# fmc.net
KiCad netlist of a schematic drawn in EAGLE
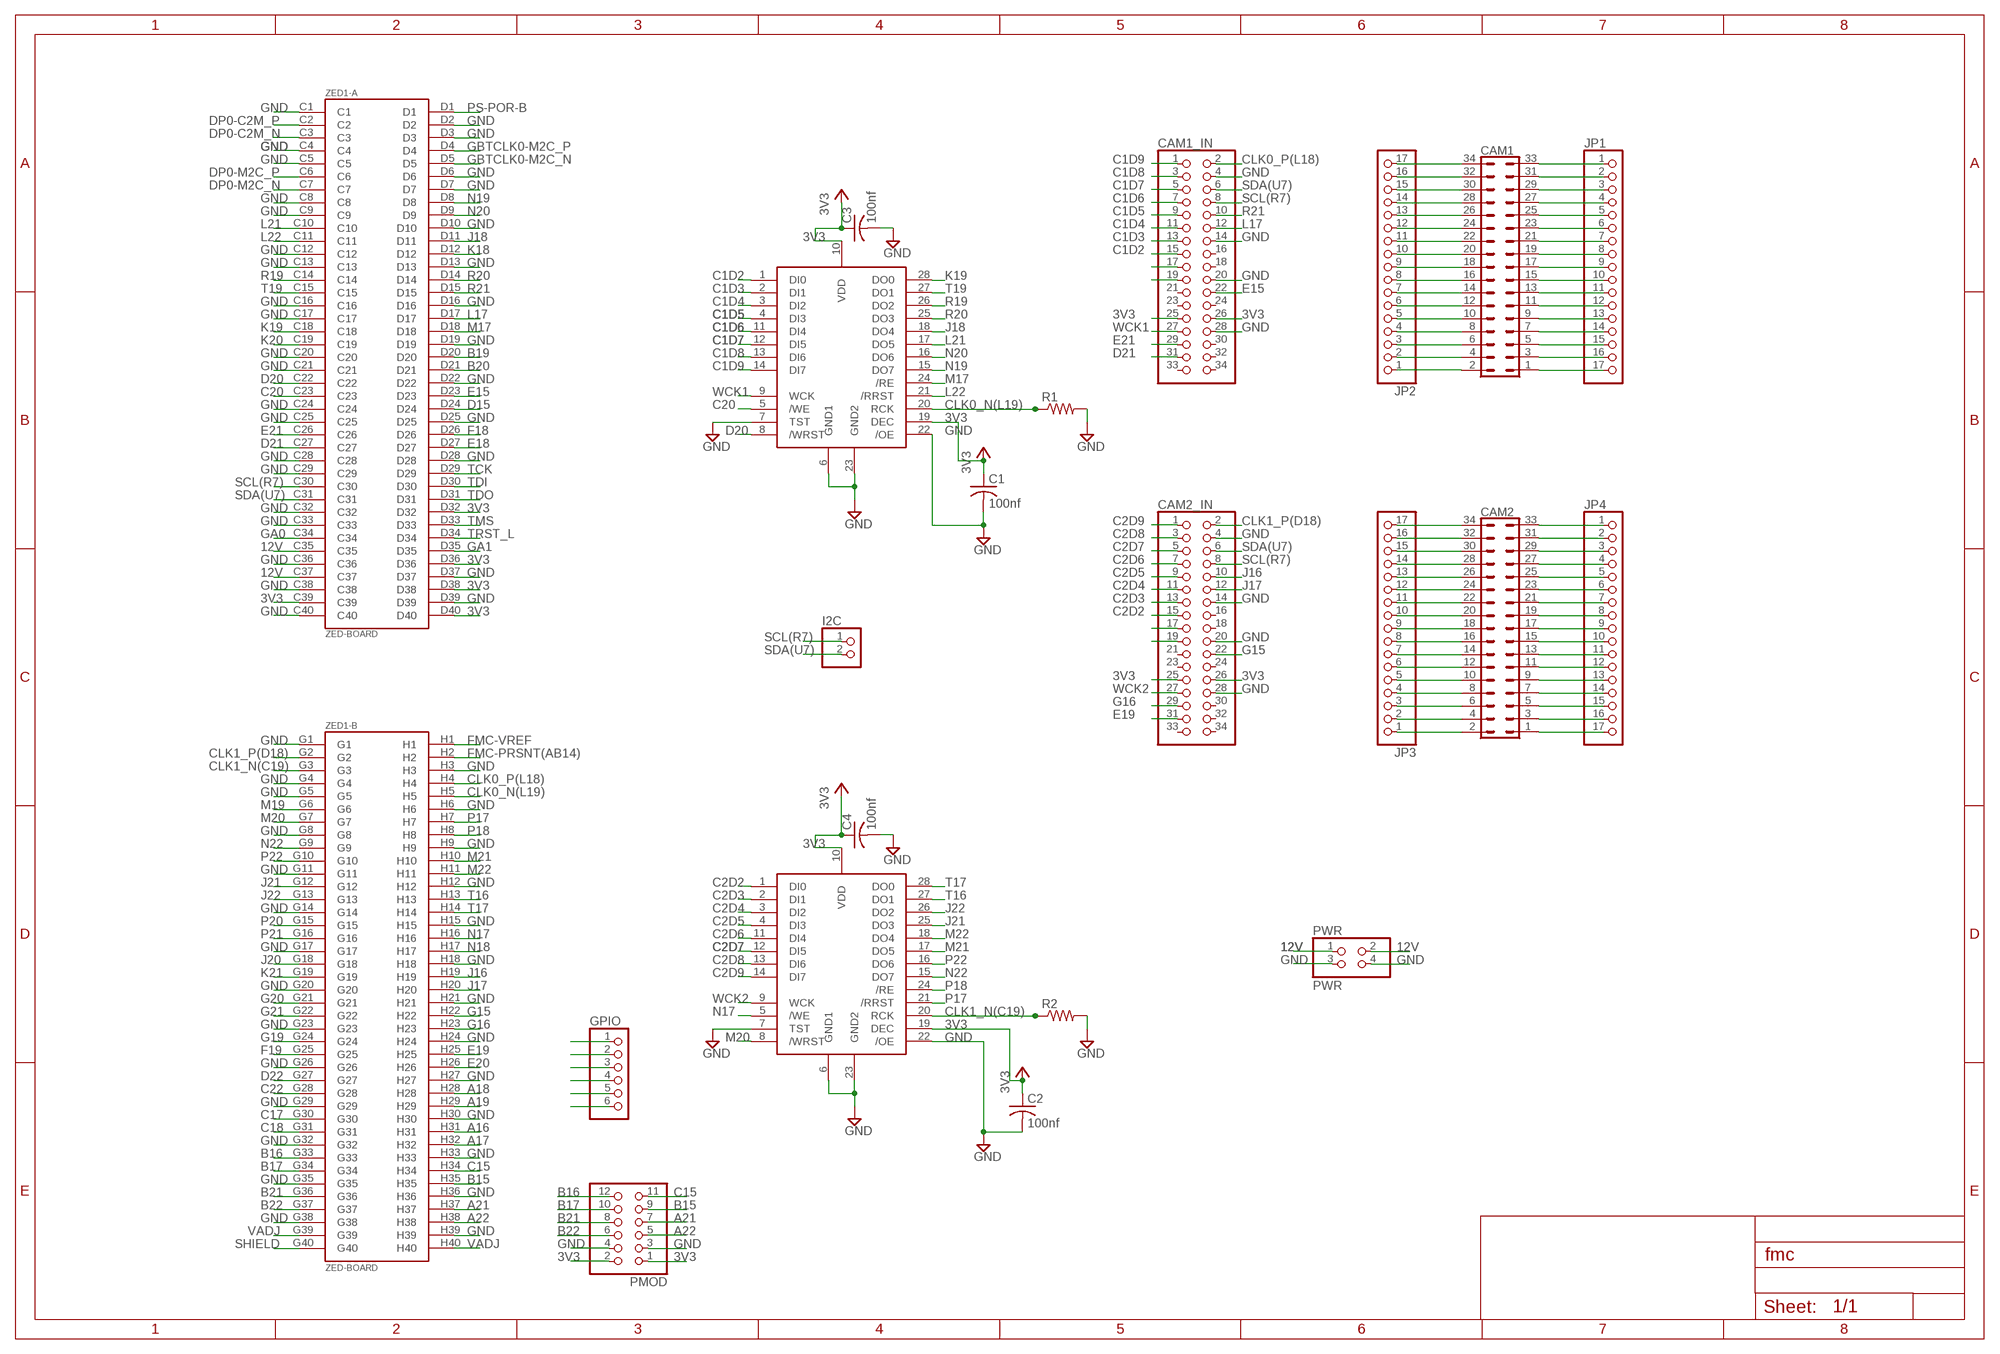
[diagram p0: schematic, sheet 1]

(export (version "E")
  (design (tool "Eeschema 10.0.6"))
  (components
    (comp (ref "AL422B_2")
      (value "CAM2_FIFO")
      (footprint "eagle-import:SOP28")
      (libsource (lib "eagle-import") (part "AL422B"))
    )
    (comp (ref "ALA22B_1")
      (value "CAM1_FIFO")
      (footprint "eagle-import:SOP28")
      (libsource (lib "eagle-import") (part "AL422B"))
    )
    (comp (ref "C1")
      (value "100nf")
      (footprint "eagle-import:C025-024X044")
      (libsource (lib "eagle-import") (part "C-US025-024X044"))
    )
    (comp (ref "C2")
      (value "100nf")
      (footprint "eagle-import:C025-024X044")
      (libsource (lib "eagle-import") (part "C-US025-024X044"))
    )
    (comp (ref "C3")
      (value "100nf")
      (footprint "eagle-import:C025-024X044")
      (libsource (lib "eagle-import") (part "C-US025-024X044"))
    )
    (comp (ref "C4")
      (value "100nf")
      (footprint "eagle-import:C025-024X044")
      (libsource (lib "eagle-import") (part "C-US025-024X044"))
    )
    (comp (ref "CAM1")
      (value "PHB_1MM27_2X17_SNT")
      (footprint "eagle-import:PHB_1MM27_2X17_SNT")
      (libsource (lib "eagle-import") (part "PHB_1MM27_2X17_SNT"))
    )
    (comp (ref "CAM1_IN")
      (value "PINHD-2X17")
      (footprint "eagle-import:2X17")
      (libsource (lib "eagle-import") (part "PINHD-2X17"))
    )
    (comp (ref "CAM2")
      (value "PHB_1MM27_2X17_SNT")
      (footprint "eagle-import:PHB_1MM27_2X17_SNT")
      (libsource (lib "eagle-import") (part "PHB_1MM27_2X17_SNT"))
    )
    (comp (ref "CAM2_IN")
      (value "PINHD-2X17")
      (footprint "eagle-import:2X17")
      (libsource (lib "eagle-import") (part "PINHD-2X17"))
    )
    (comp (ref "GPIO")
      (value "PINHD-1X6")
      (footprint "eagle-import:1X06")
      (libsource (lib "eagle-import") (part "PINHD-1X6"))
    )
    (comp (ref "I2C")
      (value "PINHD-1X2")
      (footprint "eagle-import:1X02")
      (libsource (lib "eagle-import") (part "PINHD-1X2"))
    )
    (comp (ref "JP1")
      (value "PINHD-1X17")
      (footprint "eagle-import:1X17")
      (libsource (lib "eagle-import") (part "PINHD-1X17"))
    )
    (comp (ref "JP2")
      (value "PINHD-1X17")
      (footprint "eagle-import:1X17")
      (libsource (lib "eagle-import") (part "PINHD-1X17"))
    )
    (comp (ref "JP3")
      (value "PINHD-1X17")
      (footprint "eagle-import:1X17")
      (libsource (lib "eagle-import") (part "PINHD-1X17"))
    )
    (comp (ref "JP4")
      (value "PINHD-1X17")
      (footprint "eagle-import:1X17")
      (libsource (lib "eagle-import") (part "PINHD-1X17"))
    )
    (comp (ref "PMOD")
      (value "PINHD-2X6")
      (footprint "eagle-import:2X06")
      (libsource (lib "eagle-import") (part "PINHD-2X6"))
    )
    (comp (ref "PWR")
      (value "PWR")
      (footprint "eagle-import:2X02")
      (libsource (lib "eagle-import") (part "PINHD-2X2"))
    )
    (comp (ref "R1")
      (value "R-US_M0805")
      (footprint "eagle-import:M0805")
      (libsource (lib "eagle-import") (part "R-US_M0805"))
    )
    (comp (ref "R2")
      (value "R-US_M0805")
      (footprint "eagle-import:M0805")
      (libsource (lib "eagle-import") (part "R-US_M0805"))
    )
    (comp (ref "ZED1")
      (value "ZED-BOARD")
      (footprint "eagle-import:ASP-134604-01")
      (libsource (lib "eagle-import") (part "ZED-BOARD"))
    )
  )
  (nets
    (net (code "1") (name "/12V") (class "Default")
      (node (ref "PWR") (pin "1") (pinfunction "1_1") (pintype "passive"))
      (node (ref "PWR") (pin "2") (pinfunction "2_2") (pintype "passive"))
      (node (ref "ZED1") (pin "C35") (pinfunction "C35_C35") (pintype "bidirectional"))
      (node (ref "ZED1") (pin "C37") (pinfunction "C37_C37") (pintype "bidirectional"))
    )
    (net (code "2") (name "/A16") (class "Default")
      (node (ref "GPIO") (pin "3") (pinfunction "3_3") (pintype "passive"))
      (node (ref "ZED1") (pin "H31") (pinfunction "H31_H31") (pintype "bidirectional"))
    )
    (net (code "3") (name "/A17") (class "Default")
      (node (ref "GPIO") (pin "4") (pinfunction "4_4") (pintype "passive"))
      (node (ref "ZED1") (pin "H32") (pinfunction "H32_H32") (pintype "bidirectional"))
    )
    (net (code "4") (name "/A18") (class "Default")
      (node (ref "GPIO") (pin "1") (pinfunction "1_1") (pintype "passive"))
      (node (ref "ZED1") (pin "H28") (pinfunction "H28_H28") (pintype "bidirectional"))
    )
    (net (code "5") (name "/A19") (class "Default")
      (node (ref "GPIO") (pin "2") (pinfunction "2_2") (pintype "passive"))
      (node (ref "ZED1") (pin "H29") (pinfunction "H29_H29") (pintype "bidirectional"))
    )
    (net (code "6") (name "/A21") (class "Default")
      (node (ref "PMOD") (pin "7") (pinfunction "7_7") (pintype "passive"))
      (node (ref "ZED1") (pin "H37") (pinfunction "H37_H37") (pintype "bidirectional"))
    )
    (net (code "7") (name "/A22") (class "Default")
      (node (ref "PMOD") (pin "5") (pinfunction "5_5") (pintype "passive"))
      (node (ref "ZED1") (pin "H38") (pinfunction "H38_H38") (pintype "bidirectional"))
    )
    (net (code "8") (name "/B15") (class "Default")
      (node (ref "PMOD") (pin "9") (pinfunction "9_9") (pintype "passive"))
      (node (ref "ZED1") (pin "H35") (pinfunction "H35_H35") (pintype "bidirectional"))
    )
    (net (code "9") (name "/B16") (class "Default")
      (node (ref "PMOD") (pin "12") (pinfunction "12_12") (pintype "passive"))
      (node (ref "ZED1") (pin "G33") (pinfunction "G33_G33") (pintype "bidirectional"))
    )
    (net (code "10") (name "/B17") (class "Default")
      (node (ref "PMOD") (pin "10") (pinfunction "10_10") (pintype "passive"))
      (node (ref "ZED1") (pin "G34") (pinfunction "G34_G34") (pintype "bidirectional"))
    )
    (net (code "11") (name "/B19") (class "Default")
      (node (ref "ZED1") (pin "D20") (pinfunction "D20_D20") (pintype "bidirectional"))
    )
    (net (code "12") (name "/B20") (class "Default")
      (node (ref "ZED1") (pin "D21") (pinfunction "D21_D21") (pintype "bidirectional"))
    )
    (net (code "13") (name "/B21") (class "Default")
      (node (ref "PMOD") (pin "8") (pinfunction "8_8") (pintype "passive"))
      (node (ref "ZED1") (pin "G36") (pinfunction "G36_G36") (pintype "bidirectional"))
    )
    (net (code "14") (name "/B22") (class "Default")
      (node (ref "PMOD") (pin "6") (pinfunction "6_6") (pintype "passive"))
      (node (ref "ZED1") (pin "G37") (pinfunction "G37_G37") (pintype "bidirectional"))
    )
    (net (code "15") (name "/C1D2") (class "Default")
      (node (ref "ALA22B_1") (pin "1") (pinfunction "DI0_1") (pintype "bidirectional"))
      (node (ref "CAM1_IN") (pin "15") (pinfunction "15_15") (pintype "passive"))
    )
    (net (code "16") (name "/C1D3") (class "Default")
      (node (ref "ALA22B_1") (pin "2") (pinfunction "DI1_2") (pintype "bidirectional"))
      (node (ref "CAM1_IN") (pin "13") (pinfunction "13_13") (pintype "passive"))
    )
    (net (code "17") (name "/C1D4") (class "Default")
      (node (ref "ALA22B_1") (pin "3") (pinfunction "DI2_3") (pintype "bidirectional"))
      (node (ref "CAM1_IN") (pin "11") (pinfunction "11_11") (pintype "passive"))
    )
    (net (code "18") (name "/C1D5") (class "Default")
      (node (ref "ALA22B_1") (pin "4") (pinfunction "DI3_4") (pintype "bidirectional"))
      (node (ref "CAM1_IN") (pin "9") (pinfunction "9_9") (pintype "passive"))
    )
    (net (code "19") (name "/C1D6") (class "Default")
      (node (ref "ALA22B_1") (pin "11") (pinfunction "DI4_11") (pintype "bidirectional"))
      (node (ref "CAM1_IN") (pin "7") (pinfunction "7_7") (pintype "passive"))
    )
    (net (code "20") (name "/C1D7") (class "Default")
      (node (ref "ALA22B_1") (pin "12") (pinfunction "DI5_12") (pintype "bidirectional"))
      (node (ref "CAM1_IN") (pin "5") (pinfunction "5_5") (pintype "passive"))
    )
    (net (code "21") (name "/C1D8") (class "Default")
      (node (ref "ALA22B_1") (pin "13") (pinfunction "DI6_13") (pintype "bidirectional"))
      (node (ref "CAM1_IN") (pin "3") (pinfunction "3_3") (pintype "passive"))
    )
    (net (code "22") (name "/C1D9") (class "Default")
      (node (ref "ALA22B_1") (pin "14") (pinfunction "DI7_14") (pintype "bidirectional"))
      (node (ref "CAM1_IN") (pin "1") (pinfunction "1_1") (pintype "passive"))
    )
    (net (code "23") (name "/C2D2") (class "Default")
      (node (ref "AL422B_2") (pin "1") (pinfunction "DI0_1") (pintype "bidirectional"))
      (node (ref "CAM2_IN") (pin "15") (pinfunction "15_15") (pintype "passive"))
    )
    (net (code "24") (name "/C2D3") (class "Default")
      (node (ref "AL422B_2") (pin "2") (pinfunction "DI1_2") (pintype "bidirectional"))
      (node (ref "CAM2_IN") (pin "13") (pinfunction "13_13") (pintype "passive"))
    )
    (net (code "25") (name "/C2D4") (class "Default")
      (node (ref "AL422B_2") (pin "3") (pinfunction "DI2_3") (pintype "bidirectional"))
      (node (ref "CAM2_IN") (pin "11") (pinfunction "11_11") (pintype "passive"))
    )
    (net (code "26") (name "/C2D5") (class "Default")
      (node (ref "AL422B_2") (pin "4") (pinfunction "DI3_4") (pintype "bidirectional"))
      (node (ref "CAM2_IN") (pin "9") (pinfunction "9_9") (pintype "passive"))
    )
    (net (code "27") (name "/C2D6") (class "Default")
      (node (ref "AL422B_2") (pin "11") (pinfunction "DI4_11") (pintype "bidirectional"))
      (node (ref "CAM2_IN") (pin "7") (pinfunction "7_7") (pintype "passive"))
    )
    (net (code "28") (name "/C2D7") (class "Default")
      (node (ref "AL422B_2") (pin "12") (pinfunction "DI5_12") (pintype "bidirectional"))
      (node (ref "CAM2_IN") (pin "5") (pinfunction "5_5") (pintype "passive"))
    )
    (net (code "29") (name "/C2D8") (class "Default")
      (node (ref "AL422B_2") (pin "13") (pinfunction "DI6_13") (pintype "bidirectional"))
      (node (ref "CAM2_IN") (pin "3") (pinfunction "3_3") (pintype "passive"))
    )
    (net (code "30") (name "/C2D9") (class "Default")
      (node (ref "AL422B_2") (pin "14") (pinfunction "DI7_14") (pintype "bidirectional"))
      (node (ref "CAM2_IN") (pin "1") (pinfunction "1_1") (pintype "passive"))
    )
    (net (code "31") (name "/C15") (class "Default")
      (node (ref "PMOD") (pin "11") (pinfunction "11_11") (pintype "passive"))
      (node (ref "ZED1") (pin "H34") (pinfunction "H34_H34") (pintype "bidirectional"))
    )
    (net (code "32") (name "/C17") (class "Default")
      (node (ref "ZED1") (pin "G30") (pinfunction "G30_G30") (pintype "bidirectional"))
    )
    (net (code "33") (name "/C18") (class "Default")
      (node (ref "ZED1") (pin "G31") (pinfunction "G31_G31") (pintype "bidirectional"))
    )
    (net (code "34") (name "/C20") (class "Default")
      (node (ref "ALA22B_1") (pin "5") (pinfunction "/WE_5") (pintype "bidirectional"))
      (node (ref "ZED1") (pin "C23") (pinfunction "C23_C23") (pintype "bidirectional"))
    )
    (net (code "35") (name "/C22") (class "Default")
      (node (ref "ZED1") (pin "G28") (pinfunction "G28_G28") (pintype "bidirectional"))
    )
    (net (code "36") (name "/CLK0_N(L19)") (class "Default")
      (node (ref "ALA22B_1") (pin "20") (pinfunction "RCK_20") (pintype "bidirectional"))
      (node (ref "R1") (pin "1") (pinfunction "1_1") (pintype "passive"))
      (node (ref "ZED1") (pin "H5") (pinfunction "H5_H5") (pintype "bidirectional"))
    )
    (net (code "37") (name "/CLK0_P(L18)") (class "Default")
      (node (ref "CAM1_IN") (pin "2") (pinfunction "2_2") (pintype "passive"))
      (node (ref "ZED1") (pin "H4") (pinfunction "H4_H4") (pintype "bidirectional"))
    )
    (net (code "38") (name "/CLK1_N(C19)") (class "Default")
      (node (ref "AL422B_2") (pin "20") (pinfunction "RCK_20") (pintype "bidirectional"))
      (node (ref "R2") (pin "1") (pinfunction "1_1") (pintype "passive"))
      (node (ref "ZED1") (pin "G3") (pinfunction "G3_G3") (pintype "bidirectional"))
    )
    (net (code "39") (name "/CLK1_P(D18)") (class "Default")
      (node (ref "CAM2_IN") (pin "2") (pinfunction "2_2") (pintype "passive"))
      (node (ref "ZED1") (pin "G2") (pinfunction "G2_G2") (pintype "bidirectional"))
    )
    (net (code "40") (name "/D15") (class "Default")
      (node (ref "ZED1") (pin "D24") (pinfunction "D24_D24") (pintype "bidirectional"))
    )
    (net (code "41") (name "/D20") (class "Default")
      (node (ref "ALA22B_1") (pin "8") (pinfunction "/WRST_8") (pintype "bidirectional"))
      (node (ref "ZED1") (pin "C22") (pinfunction "C22_C22") (pintype "bidirectional"))
    )
    (net (code "42") (name "/D21") (class "Default")
      (node (ref "CAM1_IN") (pin "31") (pinfunction "31_31") (pintype "passive"))
      (node (ref "ZED1") (pin "C27") (pinfunction "C27_C27") (pintype "bidirectional"))
    )
    (net (code "43") (name "/D22") (class "Default")
      (node (ref "ZED1") (pin "G27") (pinfunction "G27_G27") (pintype "bidirectional"))
    )
    (net (code "44") (name "/DP0-C2M_N") (class "Default")
      (node (ref "ZED1") (pin "C3") (pinfunction "C3_C3") (pintype "bidirectional"))
    )
    (net (code "45") (name "/DP0-C2M_P") (class "Default")
      (node (ref "ZED1") (pin "C2") (pinfunction "C2_C2") (pintype "bidirectional"))
    )
    (net (code "46") (name "/DP0-M2C_N") (class "Default")
      (node (ref "ZED1") (pin "C7") (pinfunction "C7_C7") (pintype "bidirectional"))
    )
    (net (code "47") (name "/DP0-M2C_P") (class "Default")
      (node (ref "ZED1") (pin "C6") (pinfunction "C6_C6") (pintype "bidirectional"))
    )
    (net (code "48") (name "/E15") (class "Default")
      (node (ref "CAM1_IN") (pin "22") (pinfunction "22_22") (pintype "passive"))
      (node (ref "ZED1") (pin "D23") (pinfunction "D23_D23") (pintype "bidirectional"))
    )
    (net (code "49") (name "/E18") (class "Default")
      (node (ref "ZED1") (pin "D27") (pinfunction "D27_D27") (pintype "bidirectional"))
    )
    (net (code "50") (name "/E19") (class "Default")
      (node (ref "CAM2_IN") (pin "31") (pinfunction "31_31") (pintype "passive"))
      (node (ref "ZED1") (pin "H25") (pinfunction "H25_H25") (pintype "bidirectional"))
    )
    (net (code "51") (name "/E20") (class "Default")
      (node (ref "ZED1") (pin "H26") (pinfunction "H26_H26") (pintype "bidirectional"))
    )
    (net (code "52") (name "/E21") (class "Default")
      (node (ref "CAM1_IN") (pin "29") (pinfunction "29_29") (pintype "passive"))
      (node (ref "ZED1") (pin "C26") (pinfunction "C26_C26") (pintype "bidirectional"))
    )
    (net (code "53") (name "/F18") (class "Default")
      (node (ref "ZED1") (pin "D26") (pinfunction "D26_D26") (pintype "bidirectional"))
    )
    (net (code "54") (name "/F19") (class "Default")
      (node (ref "ZED1") (pin "G25") (pinfunction "G25_G25") (pintype "bidirectional"))
    )
    (net (code "55") (name "/FMC-PRSNT(AB14)") (class "Default")
      (node (ref "ZED1") (pin "H2") (pinfunction "H2_H2") (pintype "bidirectional"))
    )
    (net (code "56") (name "/FMC-VREF") (class "Default")
      (node (ref "ZED1") (pin "H1") (pinfunction "H1_H1") (pintype "bidirectional"))
    )
    (net (code "57") (name "/G15") (class "Default")
      (node (ref "CAM2_IN") (pin "22") (pinfunction "22_22") (pintype "passive"))
      (node (ref "ZED1") (pin "H22") (pinfunction "H22_H22") (pintype "bidirectional"))
    )
    (net (code "58") (name "/G16") (class "Default")
      (node (ref "CAM2_IN") (pin "29") (pinfunction "29_29") (pintype "passive"))
      (node (ref "ZED1") (pin "H23") (pinfunction "H23_H23") (pintype "bidirectional"))
    )
    (net (code "59") (name "/G19") (class "Default")
      (node (ref "ZED1") (pin "G24") (pinfunction "G24_G24") (pintype "bidirectional"))
    )
    (net (code "60") (name "/G20") (class "Default")
      (node (ref "ZED1") (pin "G21") (pinfunction "G21_G21") (pintype "bidirectional"))
    )
    (net (code "61") (name "/G21") (class "Default")
      (node (ref "ZED1") (pin "G22") (pinfunction "G22_G22") (pintype "bidirectional"))
    )
    (net (code "62") (name "/GA0") (class "Default")
      (node (ref "ZED1") (pin "C34") (pinfunction "C34_C34") (pintype "bidirectional"))
    )
    (net (code "63") (name "/GA1") (class "Default")
      (node (ref "ZED1") (pin "D35") (pinfunction "D35_D35") (pintype "bidirectional"))
    )
    (net (code "64") (name "/GBTCLK0-M2C_N") (class "Default")
      (node (ref "ZED1") (pin "D5") (pinfunction "D5_D5") (pintype "bidirectional"))
    )
    (net (code "65") (name "/GBTCLK0-M2C_P") (class "Default")
      (node (ref "ZED1") (pin "D4") (pinfunction "D4_D4") (pintype "bidirectional"))
    )
    (net (code "66") (name "/J16") (class "Default")
      (node (ref "CAM2_IN") (pin "10") (pinfunction "10_10") (pintype "passive"))
      (node (ref "ZED1") (pin "H19") (pinfunction "H19_H19") (pintype "bidirectional"))
    )
    (net (code "67") (name "/J17") (class "Default")
      (node (ref "CAM2_IN") (pin "12") (pinfunction "12_12") (pintype "passive"))
      (node (ref "ZED1") (pin "H20") (pinfunction "H20_H20") (pintype "bidirectional"))
    )
    (net (code "68") (name "/J18") (class "Default")
      (node (ref "ALA22B_1") (pin "18") (pinfunction "DO4_18") (pintype "bidirectional"))
      (node (ref "ZED1") (pin "D11") (pinfunction "D11_D11") (pintype "bidirectional"))
    )
    (net (code "69") (name "/J20") (class "Default")
      (node (ref "ZED1") (pin "G18") (pinfunction "G18_G18") (pintype "bidirectional"))
    )
    (net (code "70") (name "/J21") (class "Default")
      (node (ref "AL422B_2") (pin "25") (pinfunction "DO3_25") (pintype "bidirectional"))
      (node (ref "ZED1") (pin "G12") (pinfunction "G12_G12") (pintype "bidirectional"))
    )
    (net (code "71") (name "/J22") (class "Default")
      (node (ref "AL422B_2") (pin "26") (pinfunction "DO2_26") (pintype "bidirectional"))
      (node (ref "ZED1") (pin "G13") (pinfunction "G13_G13") (pintype "bidirectional"))
    )
    (net (code "72") (name "/K18") (class "Default")
      (node (ref "ZED1") (pin "D12") (pinfunction "D12_D12") (pintype "bidirectional"))
    )
    (net (code "73") (name "/K19") (class "Default")
      (node (ref "ALA22B_1") (pin "28") (pinfunction "DO0_28") (pintype "bidirectional"))
      (node (ref "ZED1") (pin "C18") (pinfunction "C18_C18") (pintype "bidirectional"))
    )
    (net (code "74") (name "/K20") (class "Default")
      (node (ref "ZED1") (pin "C19") (pinfunction "C19_C19") (pintype "bidirectional"))
    )
    (net (code "75") (name "/K21") (class "Default")
      (node (ref "ZED1") (pin "G19") (pinfunction "G19_G19") (pintype "bidirectional"))
    )
    (net (code "76") (name "/L17") (class "Default")
      (node (ref "CAM1_IN") (pin "12") (pinfunction "12_12") (pintype "passive"))
      (node (ref "ZED1") (pin "D17") (pinfunction "D17_D17") (pintype "bidirectional"))
    )
    (net (code "77") (name "/L21") (class "Default")
      (node (ref "ALA22B_1") (pin "17") (pinfunction "DO5_17") (pintype "bidirectional"))
      (node (ref "ZED1") (pin "C10") (pinfunction "C10_C10") (pintype "bidirectional"))
    )
    (net (code "78") (name "/L22") (class "Default")
      (node (ref "ALA22B_1") (pin "21") (pinfunction "/RRST_21") (pintype "bidirectional"))
      (node (ref "ZED1") (pin "C11") (pinfunction "C11_C11") (pintype "bidirectional"))
    )
    (net (code "79") (name "/M17") (class "Default")
      (node (ref "ALA22B_1") (pin "24") (pinfunction "/RE_24") (pintype "bidirectional"))
      (node (ref "ZED1") (pin "D18") (pinfunction "D18_D18") (pintype "bidirectional"))
    )
    (net (code "80") (name "/M19") (class "Default")
      (node (ref "ZED1") (pin "G6") (pinfunction "G6_G6") (pintype "bidirectional"))
    )
    (net (code "81") (name "/M20") (class "Default")
      (node (ref "AL422B_2") (pin "8") (pinfunction "/WRST_8") (pintype "bidirectional"))
      (node (ref "ZED1") (pin "G7") (pinfunction "G7_G7") (pintype "bidirectional"))
    )
    (net (code "82") (name "/M21") (class "Default")
      (node (ref "AL422B_2") (pin "17") (pinfunction "DO5_17") (pintype "bidirectional"))
      (node (ref "ZED1") (pin "H10") (pinfunction "H10_H10") (pintype "bidirectional"))
    )
    (net (code "83") (name "/M22") (class "Default")
      (node (ref "AL422B_2") (pin "18") (pinfunction "DO4_18") (pintype "bidirectional"))
      (node (ref "ZED1") (pin "H11") (pinfunction "H11_H11") (pintype "bidirectional"))
    )
    (net (code "84") (name "/N17") (class "Default")
      (node (ref "AL422B_2") (pin "5") (pinfunction "/WE_5") (pintype "bidirectional"))
      (node (ref "ZED1") (pin "H16") (pinfunction "H16_H16") (pintype "bidirectional"))
    )
    (net (code "85") (name "/N18") (class "Default")
      (node (ref "ZED1") (pin "H17") (pinfunction "H17_H17") (pintype "bidirectional"))
    )
    (net (code "86") (name "/N19") (class "Default")
      (node (ref "ALA22B_1") (pin "15") (pinfunction "DO7_15") (pintype "bidirectional"))
      (node (ref "ZED1") (pin "D8") (pinfunction "D8_D8") (pintype "bidirectional"))
    )
    (net (code "87") (name "/N20") (class "Default")
      (node (ref "ALA22B_1") (pin "16") (pinfunction "DO6_16") (pintype "bidirectional"))
      (node (ref "ZED1") (pin "D9") (pinfunction "D9_D9") (pintype "bidirectional"))
    )
    (net (code "88") (name "/N22") (class "Default")
      (node (ref "AL422B_2") (pin "15") (pinfunction "DO7_15") (pintype "bidirectional"))
      (node (ref "ZED1") (pin "G9") (pinfunction "G9_G9") (pintype "bidirectional"))
    )
    (net (code "89") (name "/P17") (class "Default")
      (node (ref "AL422B_2") (pin "21") (pinfunction "/RRST_21") (pintype "bidirectional"))
      (node (ref "ZED1") (pin "H7") (pinfunction "H7_H7") (pintype "bidirectional"))
    )
    (net (code "90") (name "/P18") (class "Default")
      (node (ref "AL422B_2") (pin "24") (pinfunction "/RE_24") (pintype "bidirectional"))
      (node (ref "ZED1") (pin "H8") (pinfunction "H8_H8") (pintype "bidirectional"))
    )
    (net (code "91") (name "/P20") (class "Default")
      (node (ref "ZED1") (pin "G15") (pinfunction "G15_G15") (pintype "bidirectional"))
    )
    (net (code "92") (name "/P21") (class "Default")
      (node (ref "ZED1") (pin "G16") (pinfunction "G16_G16") (pintype "bidirectional"))
    )
    (net (code "93") (name "/P22") (class "Default")
      (node (ref "AL422B_2") (pin "16") (pinfunction "DO6_16") (pintype "bidirectional"))
      (node (ref "ZED1") (pin "G10") (pinfunction "G10_G10") (pintype "bidirectional"))
    )
    (net (code "94") (name "/PS-POR-B") (class "Default")
      (node (ref "ZED1") (pin "D1") (pinfunction "D1_D1") (pintype "bidirectional"))
    )
    (net (code "95") (name "/R19") (class "Default")
      (node (ref "ALA22B_1") (pin "26") (pinfunction "DO2_26") (pintype "bidirectional"))
      (node (ref "ZED1") (pin "C14") (pinfunction "C14_C14") (pintype "bidirectional"))
    )
    (net (code "96") (name "/R20") (class "Default")
      (node (ref "ALA22B_1") (pin "25") (pinfunction "DO3_25") (pintype "bidirectional"))
      (node (ref "ZED1") (pin "D14") (pinfunction "D14_D14") (pintype "bidirectional"))
    )
    (net (code "97") (name "/R21") (class "Default")
      (node (ref "CAM1_IN") (pin "10") (pinfunction "10_10") (pintype "passive"))
      (node (ref "ZED1") (pin "D15") (pinfunction "D15_D15") (pintype "bidirectional"))
    )
    (net (code "98") (name "/SCL(R7)") (class "Default")
      (node (ref "CAM1_IN") (pin "8") (pinfunction "8_8") (pintype "passive"))
      (node (ref "CAM2_IN") (pin "8") (pinfunction "8_8") (pintype "passive"))
      (node (ref "I2C") (pin "1") (pinfunction "1_1") (pintype "passive"))
      (node (ref "ZED1") (pin "C30") (pinfunction "C30_C30") (pintype "bidirectional"))
    )
    (net (code "99") (name "/SDA(U7)") (class "Default")
      (node (ref "CAM1_IN") (pin "6") (pinfunction "6_6") (pintype "passive"))
      (node (ref "CAM2_IN") (pin "6") (pinfunction "6_6") (pintype "passive"))
      (node (ref "I2C") (pin "2") (pinfunction "2_2") (pintype "passive"))
      (node (ref "ZED1") (pin "C31") (pinfunction "C31_C31") (pintype "bidirectional"))
    )
    (net (code "100") (name "/SHIELD") (class "Default")
      (node (ref "ZED1") (pin "G40") (pinfunction "G40_G40") (pintype "bidirectional"))
    )
    (net (code "101") (name "/T16") (class "Default")
      (node (ref "AL422B_2") (pin "27") (pinfunction "DO1_27") (pintype "bidirectional"))
      (node (ref "ZED1") (pin "H13") (pinfunction "H13_H13") (pintype "bidirectional"))
    )
    (net (code "102") (name "/T17") (class "Default")
      (node (ref "AL422B_2") (pin "28") (pinfunction "DO0_28") (pintype "bidirectional"))
      (node (ref "ZED1") (pin "H14") (pinfunction "H14_H14") (pintype "bidirectional"))
    )
    (net (code "103") (name "/T19") (class "Default")
      (node (ref "ALA22B_1") (pin "27") (pinfunction "DO1_27") (pintype "bidirectional"))
      (node (ref "ZED1") (pin "C15") (pinfunction "C15_C15") (pintype "bidirectional"))
    )
    (net (code "104") (name "/TCK") (class "Default")
      (node (ref "ZED1") (pin "D29") (pinfunction "D29_D29") (pintype "bidirectional"))
    )
    (net (code "105") (name "/TDI") (class "Default")
      (node (ref "ZED1") (pin "D30") (pinfunction "D30_D30") (pintype "bidirectional"))
    )
    (net (code "106") (name "/TDO") (class "Default")
      (node (ref "ZED1") (pin "D31") (pinfunction "D31_D31") (pintype "bidirectional"))
    )
    (net (code "107") (name "/TMS") (class "Default")
      (node (ref "ZED1") (pin "D33") (pinfunction "D33_D33") (pintype "bidirectional"))
    )
    (net (code "108") (name "/TRST_L") (class "Default")
      (node (ref "ZED1") (pin "D34") (pinfunction "D34_D34") (pintype "bidirectional"))
    )
    (net (code "109") (name "/VADJ") (class "Default")
      (node (ref "ZED1") (pin "G39") (pinfunction "G39_G39") (pintype "bidirectional"))
      (node (ref "ZED1") (pin "H40") (pinfunction "H40_H40") (pintype "bidirectional"))
    )
    (net (code "110") (name "/WCK1") (class "Default")
      (node (ref "ALA22B_1") (pin "9") (pinfunction "WCK_9") (pintype "bidirectional"))
      (node (ref "CAM1_IN") (pin "27") (pinfunction "27_27") (pintype "passive"))
    )
    (net (code "111") (name "/WCK2") (class "Default")
      (node (ref "AL422B_2") (pin "9") (pinfunction "WCK_9") (pintype "bidirectional"))
      (node (ref "CAM2_IN") (pin "27") (pinfunction "27_27") (pintype "passive"))
    )
    (net (code "112") (name "3V3") (class "Default")
      (node (ref "AL422B_2") (pin "10") (pinfunction "VDD_10") (pintype "power_in"))
      (node (ref "AL422B_2") (pin "19") (pinfunction "DEC_19") (pintype "bidirectional"))
      (node (ref "ALA22B_1") (pin "10") (pinfunction "VDD_10") (pintype "power_in"))
      (node (ref "ALA22B_1") (pin "19") (pinfunction "DEC_19") (pintype "bidirectional"))
      (node (ref "C1") (pin "1") (pinfunction "1_1") (pintype "passive"))
      (node (ref "C2") (pin "1") (pinfunction "1_1") (pintype "passive"))
      (node (ref "C3") (pin "1") (pinfunction "1_1") (pintype "passive"))
      (node (ref "C4") (pin "1") (pinfunction "1_1") (pintype "passive"))
      (node (ref "CAM1_IN") (pin "25") (pinfunction "25_25") (pintype "passive"))
      (node (ref "CAM1_IN") (pin "26") (pinfunction "26_26") (pintype "passive"))
      (node (ref "CAM2_IN") (pin "25") (pinfunction "25_25") (pintype "passive"))
      (node (ref "CAM2_IN") (pin "26") (pinfunction "26_26") (pintype "passive"))
      (node (ref "GPIO") (pin "6") (pinfunction "6_6") (pintype "passive"))
      (node (ref "PMOD") (pin "1") (pinfunction "1_1") (pintype "passive"))
      (node (ref "PMOD") (pin "2") (pinfunction "2_2") (pintype "passive"))
      (node (ref "ZED1") (pin "C39") (pinfunction "C39_C39") (pintype "bidirectional"))
      (node (ref "ZED1") (pin "D32") (pinfunction "D32_D32") (pintype "bidirectional"))
      (node (ref "ZED1") (pin "D36") (pinfunction "D36_D36") (pintype "bidirectional"))
      (node (ref "ZED1") (pin "D38") (pinfunction "D38_D38") (pintype "bidirectional"))
      (node (ref "ZED1") (pin "D40") (pinfunction "D40_D40") (pintype "bidirectional"))
    )
    (net (code "113") (name "GND") (class "Default")
      (node (ref "AL422B_2") (pin "22") (pinfunction "/OE_22") (pintype "bidirectional"))
      (node (ref "AL422B_2") (pin "23") (pinfunction "GND2_23") (pintype "power_in"))
      (node (ref "AL422B_2") (pin "6") (pinfunction "GND1_6") (pintype "power_in"))
      (node (ref "AL422B_2") (pin "7") (pinfunction "TST_7") (pintype "bidirectional"))
      (node (ref "ALA22B_1") (pin "22") (pinfunction "/OE_22") (pintype "bidirectional"))
      (node (ref "ALA22B_1") (pin "23") (pinfunction "GND2_23") (pintype "power_in"))
      (node (ref "ALA22B_1") (pin "6") (pinfunction "GND1_6") (pintype "power_in"))
      (node (ref "ALA22B_1") (pin "7") (pinfunction "TST_7") (pintype "bidirectional"))
      (node (ref "C1") (pin "2") (pinfunction "2_2") (pintype "passive"))
      (node (ref "C2") (pin "2") (pinfunction "2_2") (pintype "passive"))
      (node (ref "C3") (pin "2") (pinfunction "2_2") (pintype "passive"))
      (node (ref "C4") (pin "2") (pinfunction "2_2") (pintype "passive"))
      (node (ref "CAM1_IN") (pin "14") (pinfunction "14_14") (pintype "passive"))
      (node (ref "CAM1_IN") (pin "20") (pinfunction "20_20") (pintype "passive"))
      (node (ref "CAM1_IN") (pin "28") (pinfunction "28_28") (pintype "passive"))
      (node (ref "CAM1_IN") (pin "4") (pinfunction "4_4") (pintype "passive"))
      (node (ref "CAM2_IN") (pin "14") (pinfunction "14_14") (pintype "passive"))
      (node (ref "CAM2_IN") (pin "20") (pinfunction "20_20") (pintype "passive"))
      (node (ref "CAM2_IN") (pin "28") (pinfunction "28_28") (pintype "passive"))
      (node (ref "CAM2_IN") (pin "4") (pinfunction "4_4") (pintype "passive"))
      (node (ref "GPIO") (pin "5") (pinfunction "5_5") (pintype "passive"))
      (node (ref "PMOD") (pin "3") (pinfunction "3_3") (pintype "passive"))
      (node (ref "PMOD") (pin "4") (pinfunction "4_4") (pintype "passive"))
      (node (ref "PWR") (pin "3") (pinfunction "3_3") (pintype "passive"))
      (node (ref "PWR") (pin "4") (pinfunction "4_4") (pintype "passive"))
      (node (ref "R1") (pin "2") (pinfunction "2_2") (pintype "passive"))
      (node (ref "R2") (pin "2") (pinfunction "2_2") (pintype "passive"))
      (node (ref "ZED1") (pin "C1") (pinfunction "C1_C1") (pintype "bidirectional"))
      (node (ref "ZED1") (pin "C12") (pinfunction "C12_C12") (pintype "bidirectional"))
      (node (ref "ZED1") (pin "C13") (pinfunction "C13_C13") (pintype "bidirectional"))
      (node (ref "ZED1") (pin "C16") (pinfunction "C16_C16") (pintype "bidirectional"))
      (node (ref "ZED1") (pin "C17") (pinfunction "C17_C17") (pintype "bidirectional"))
      (node (ref "ZED1") (pin "C20") (pinfunction "C20_C20") (pintype "bidirectional"))
      (node (ref "ZED1") (pin "C21") (pinfunction "C21_C21") (pintype "bidirectional"))
      (node (ref "ZED1") (pin "C24") (pinfunction "C24_C24") (pintype "bidirectional"))
      (node (ref "ZED1") (pin "C25") (pinfunction "C25_C25") (pintype "bidirectional"))
      (node (ref "ZED1") (pin "C28") (pinfunction "C28_C28") (pintype "bidirectional"))
      (node (ref "ZED1") (pin "C29") (pinfunction "C29_C29") (pintype "bidirectional"))
      (node (ref "ZED1") (pin "C32") (pinfunction "C32_C32") (pintype "bidirectional"))
      (node (ref "ZED1") (pin "C33") (pinfunction "C33_C33") (pintype "bidirectional"))
      (node (ref "ZED1") (pin "C36") (pinfunction "C36_C36") (pintype "bidirectional"))
      (node (ref "ZED1") (pin "C38") (pinfunction "C38_C38") (pintype "bidirectional"))
      (node (ref "ZED1") (pin "C4") (pinfunction "C4_C4") (pintype "bidirectional"))
      (node (ref "ZED1") (pin "C40") (pinfunction "C40_C40") (pintype "bidirectional"))
      (node (ref "ZED1") (pin "C5") (pinfunction "C5_C5") (pintype "bidirectional"))
      (node (ref "ZED1") (pin "C8") (pinfunction "C8_C8") (pintype "bidirectional"))
      (node (ref "ZED1") (pin "C9") (pinfunction "C9_C9") (pintype "bidirectional"))
      (node (ref "ZED1") (pin "D10") (pinfunction "D10_D10") (pintype "bidirectional"))
      (node (ref "ZED1") (pin "D13") (pinfunction "D13_D13") (pintype "bidirectional"))
      (node (ref "ZED1") (pin "D16") (pinfunction "D16_D16") (pintype "bidirectional"))
      (node (ref "ZED1") (pin "D19") (pinfunction "D19_D19") (pintype "bidirectional"))
      (node (ref "ZED1") (pin "D2") (pinfunction "D2_D2") (pintype "bidirectional"))
      (node (ref "ZED1") (pin "D22") (pinfunction "D22_D22") (pintype "bidirectional"))
      (node (ref "ZED1") (pin "D25") (pinfunction "D25_D25") (pintype "bidirectional"))
      (node (ref "ZED1") (pin "D28") (pinfunction "D28_D28") (pintype "bidirectional"))
      (node (ref "ZED1") (pin "D3") (pinfunction "D3_D3") (pintype "bidirectional"))
      (node (ref "ZED1") (pin "D37") (pinfunction "D37_D37") (pintype "bidirectional"))
      (node (ref "ZED1") (pin "D39") (pinfunction "D39_D39") (pintype "bidirectional"))
      (node (ref "ZED1") (pin "D6") (pinfunction "D6_D6") (pintype "bidirectional"))
      (node (ref "ZED1") (pin "D7") (pinfunction "D7_D7") (pintype "bidirectional"))
      (node (ref "ZED1") (pin "G1") (pinfunction "G1_G1") (pintype "bidirectional"))
      (node (ref "ZED1") (pin "G11") (pinfunction "G11_G11") (pintype "bidirectional"))
      (node (ref "ZED1") (pin "G14") (pinfunction "G14_G14") (pintype "bidirectional"))
      (node (ref "ZED1") (pin "G17") (pinfunction "G17_G17") (pintype "bidirectional"))
      (node (ref "ZED1") (pin "G20") (pinfunction "G20_G20") (pintype "bidirectional"))
      (node (ref "ZED1") (pin "G23") (pinfunction "G23_G23") (pintype "bidirectional"))
      (node (ref "ZED1") (pin "G26") (pinfunction "G26_G26") (pintype "bidirectional"))
      (node (ref "ZED1") (pin "G29") (pinfunction "G29_G29") (pintype "bidirectional"))
      (node (ref "ZED1") (pin "G32") (pinfunction "G32_G32") (pintype "bidirectional"))
      (node (ref "ZED1") (pin "G35") (pinfunction "G35_G35") (pintype "bidirectional"))
      (node (ref "ZED1") (pin "G38") (pinfunction "G38_G38") (pintype "bidirectional"))
      (node (ref "ZED1") (pin "G4") (pinfunction "G4_G4") (pintype "bidirectional"))
      (node (ref "ZED1") (pin "G5") (pinfunction "G5_G5") (pintype "bidirectional"))
      (node (ref "ZED1") (pin "G8") (pinfunction "G8_G8") (pintype "bidirectional"))
      (node (ref "ZED1") (pin "H12") (pinfunction "H12_H12") (pintype "bidirectional"))
      (node (ref "ZED1") (pin "H15") (pinfunction "H15_H15") (pintype "bidirectional"))
      (node (ref "ZED1") (pin "H18") (pinfunction "H18_H18") (pintype "bidirectional"))
      (node (ref "ZED1") (pin "H21") (pinfunction "H21_H21") (pintype "bidirectional"))
      (node (ref "ZED1") (pin "H24") (pinfunction "H24_H24") (pintype "bidirectional"))
      (node (ref "ZED1") (pin "H27") (pinfunction "H27_H27") (pintype "bidirectional"))
      (node (ref "ZED1") (pin "H3") (pinfunction "H3_H3") (pintype "bidirectional"))
      (node (ref "ZED1") (pin "H30") (pinfunction "H30_H30") (pintype "bidirectional"))
      (node (ref "ZED1") (pin "H33") (pinfunction "H33_H33") (pintype "bidirectional"))
      (node (ref "ZED1") (pin "H36") (pinfunction "H36_H36") (pintype "bidirectional"))
      (node (ref "ZED1") (pin "H39") (pinfunction "H39_H39") (pintype "bidirectional"))
      (node (ref "ZED1") (pin "H6") (pinfunction "H6_H6") (pintype "bidirectional"))
      (node (ref "ZED1") (pin "H9") (pinfunction "H9_H9") (pintype "bidirectional"))
    )
    (net (code "114") (name "Net-(CAM1-Pad1)") (class "Default")
      (node (ref "CAM1") (pin "1") (pinfunction "1_1") (pintype "passive"))
      (node (ref "JP1") (pin "17") (pinfunction "17_17") (pintype "passive"))
    )
    (net (code "115") (name "Net-(CAM1-Pad2)") (class "Default")
      (node (ref "CAM1") (pin "2") (pinfunction "2_2") (pintype "passive"))
      (node (ref "JP2") (pin "1") (pinfunction "1_1") (pintype "passive"))
    )
    (net (code "116") (name "Net-(CAM1-Pad3)") (class "Default")
      (node (ref "CAM1") (pin "3") (pinfunction "3_3") (pintype "passive"))
      (node (ref "JP1") (pin "16") (pinfunction "16_16") (pintype "passive"))
    )
    (net (code "117") (name "Net-(CAM1-Pad4)") (class "Default")
      (node (ref "CAM1") (pin "4") (pinfunction "4_4") (pintype "passive"))
      (node (ref "JP2") (pin "2") (pinfunction "2_2") (pintype "passive"))
    )
    (net (code "118") (name "Net-(CAM1-Pad5)") (class "Default")
      (node (ref "CAM1") (pin "5") (pinfunction "5_5") (pintype "passive"))
      (node (ref "JP1") (pin "15") (pinfunction "15_15") (pintype "passive"))
    )
    (net (code "119") (name "Net-(CAM1-Pad6)") (class "Default")
      (node (ref "CAM1") (pin "6") (pinfunction "6_6") (pintype "passive"))
      (node (ref "JP2") (pin "3") (pinfunction "3_3") (pintype "passive"))
    )
    (net (code "120") (name "Net-(CAM1-Pad7)") (class "Default")
      (node (ref "CAM1") (pin "7") (pinfunction "7_7") (pintype "passive"))
      (node (ref "JP1") (pin "14") (pinfunction "14_14") (pintype "passive"))
    )
    (net (code "121") (name "Net-(CAM1-Pad8)") (class "Default")
      (node (ref "CAM1") (pin "8") (pinfunction "8_8") (pintype "passive"))
      (node (ref "JP2") (pin "4") (pinfunction "4_4") (pintype "passive"))
    )
    (net (code "122") (name "Net-(CAM1-Pad9)") (class "Default")
      (node (ref "CAM1") (pin "9") (pinfunction "9_9") (pintype "passive"))
      (node (ref "JP1") (pin "13") (pinfunction "13_13") (pintype "passive"))
    )
    (net (code "123") (name "Net-(CAM1-Pad10)") (class "Default")
      (node (ref "CAM1") (pin "10") (pinfunction "10_10") (pintype "passive"))
      (node (ref "JP2") (pin "5") (pinfunction "5_5") (pintype "passive"))
    )
    (net (code "124") (name "Net-(CAM1-Pad11)") (class "Default")
      (node (ref "CAM1") (pin "11") (pinfunction "11_11") (pintype "passive"))
      (node (ref "JP1") (pin "12") (pinfunction "12_12") (pintype "passive"))
    )
    (net (code "125") (name "Net-(CAM1-Pad12)") (class "Default")
      (node (ref "CAM1") (pin "12") (pinfunction "12_12") (pintype "passive"))
      (node (ref "JP2") (pin "6") (pinfunction "6_6") (pintype "passive"))
    )
    (net (code "126") (name "Net-(CAM1-Pad13)") (class "Default")
      (node (ref "CAM1") (pin "13") (pinfunction "13_13") (pintype "passive"))
      (node (ref "JP1") (pin "11") (pinfunction "11_11") (pintype "passive"))
    )
    (net (code "127") (name "Net-(CAM1-Pad14)") (class "Default")
      (node (ref "CAM1") (pin "14") (pinfunction "14_14") (pintype "passive"))
      (node (ref "JP2") (pin "7") (pinfunction "7_7") (pintype "passive"))
    )
    (net (code "128") (name "Net-(CAM1-Pad15)") (class "Default")
      (node (ref "CAM1") (pin "15") (pinfunction "15_15") (pintype "passive"))
      (node (ref "JP1") (pin "10") (pinfunction "10_10") (pintype "passive"))
    )
    (net (code "129") (name "Net-(CAM1-Pad16)") (class "Default")
      (node (ref "CAM1") (pin "16") (pinfunction "16_16") (pintype "passive"))
      (node (ref "JP2") (pin "8") (pinfunction "8_8") (pintype "passive"))
    )
    (net (code "130") (name "Net-(CAM1-Pad17)") (class "Default")
      (node (ref "CAM1") (pin "17") (pinfunction "17_17") (pintype "passive"))
      (node (ref "JP1") (pin "9") (pinfunction "9_9") (pintype "passive"))
    )
    (net (code "131") (name "Net-(CAM1-Pad18)") (class "Default")
      (node (ref "CAM1") (pin "18") (pinfunction "18_18") (pintype "passive"))
      (node (ref "JP2") (pin "9") (pinfunction "9_9") (pintype "passive"))
    )
    (net (code "132") (name "Net-(CAM1-Pad19)") (class "Default")
      (node (ref "CAM1") (pin "19") (pinfunction "19_19") (pintype "passive"))
      (node (ref "JP1") (pin "8") (pinfunction "8_8") (pintype "passive"))
    )
    (net (code "133") (name "Net-(CAM1-Pad20)") (class "Default")
      (node (ref "CAM1") (pin "20") (pinfunction "20_20") (pintype "passive"))
      (node (ref "JP2") (pin "10") (pinfunction "10_10") (pintype "passive"))
    )
    (net (code "134") (name "Net-(CAM1-Pad21)") (class "Default")
      (node (ref "CAM1") (pin "21") (pinfunction "21_21") (pintype "passive"))
      (node (ref "JP1") (pin "7") (pinfunction "7_7") (pintype "passive"))
    )
    (net (code "135") (name "Net-(CAM1-Pad22)") (class "Default")
      (node (ref "CAM1") (pin "22") (pinfunction "22_22") (pintype "passive"))
      (node (ref "JP2") (pin "11") (pinfunction "11_11") (pintype "passive"))
    )
    (net (code "136") (name "Net-(CAM1-Pad23)") (class "Default")
      (node (ref "CAM1") (pin "23") (pinfunction "23_23") (pintype "passive"))
      (node (ref "JP1") (pin "6") (pinfunction "6_6") (pintype "passive"))
    )
    (net (code "137") (name "Net-(CAM1-Pad24)") (class "Default")
      (node (ref "CAM1") (pin "24") (pinfunction "24_24") (pintype "passive"))
      (node (ref "JP2") (pin "12") (pinfunction "12_12") (pintype "passive"))
    )
    (net (code "138") (name "Net-(CAM1-Pad25)") (class "Default")
      (node (ref "CAM1") (pin "25") (pinfunction "25_25") (pintype "passive"))
      (node (ref "JP1") (pin "5") (pinfunction "5_5") (pintype "passive"))
    )
    (net (code "139") (name "Net-(CAM1-Pad26)") (class "Default")
      (node (ref "CAM1") (pin "26") (pinfunction "26_26") (pintype "passive"))
      (node (ref "JP2") (pin "13") (pinfunction "13_13") (pintype "passive"))
    )
    (net (code "140") (name "Net-(CAM1-Pad27)") (class "Default")
      (node (ref "CAM1") (pin "27") (pinfunction "27_27") (pintype "passive"))
      (node (ref "JP1") (pin "4") (pinfunction "4_4") (pintype "passive"))
    )
    (net (code "141") (name "Net-(CAM1-Pad28)") (class "Default")
      (node (ref "CAM1") (pin "28") (pinfunction "28_28") (pintype "passive"))
      (node (ref "JP2") (pin "14") (pinfunction "14_14") (pintype "passive"))
    )
    (net (code "142") (name "Net-(CAM1-Pad29)") (class "Default")
      (node (ref "CAM1") (pin "29") (pinfunction "29_29") (pintype "passive"))
      (node (ref "JP1") (pin "3") (pinfunction "3_3") (pintype "passive"))
    )
    (net (code "143") (name "Net-(CAM1-Pad30)") (class "Default")
      (node (ref "CAM1") (pin "30") (pinfunction "30_30") (pintype "passive"))
      (node (ref "JP2") (pin "15") (pinfunction "15_15") (pintype "passive"))
    )
    (net (code "144") (name "Net-(CAM1-Pad31)") (class "Default")
      (node (ref "CAM1") (pin "31") (pinfunction "31_31") (pintype "passive"))
      (node (ref "JP1") (pin "2") (pinfunction "2_2") (pintype "passive"))
    )
    (net (code "145") (name "Net-(CAM1-Pad32)") (class "Default")
      (node (ref "CAM1") (pin "32") (pinfunction "32_32") (pintype "passive"))
      (node (ref "JP2") (pin "16") (pinfunction "16_16") (pintype "passive"))
    )
    (net (code "146") (name "Net-(CAM1-Pad33)") (class "Default")
      (node (ref "CAM1") (pin "33") (pinfunction "33_33") (pintype "passive"))
      (node (ref "JP1") (pin "1") (pinfunction "1_1") (pintype "passive"))
    )
    (net (code "147") (name "Net-(CAM1-Pad34)") (class "Default")
      (node (ref "CAM1") (pin "34") (pinfunction "34_34") (pintype "passive"))
      (node (ref "JP2") (pin "17") (pinfunction "17_17") (pintype "passive"))
    )
    (net (code "148") (name "Net-(CAM2-Pad1)") (class "Default")
      (node (ref "CAM2") (pin "1") (pinfunction "1_1") (pintype "passive"))
      (node (ref "JP4") (pin "17") (pinfunction "17_17") (pintype "passive"))
    )
    (net (code "149") (name "Net-(CAM2-Pad2)") (class "Default")
      (node (ref "CAM2") (pin "2") (pinfunction "2_2") (pintype "passive"))
      (node (ref "JP3") (pin "1") (pinfunction "1_1") (pintype "passive"))
    )
    (net (code "150") (name "Net-(CAM2-Pad3)") (class "Default")
      (node (ref "CAM2") (pin "3") (pinfunction "3_3") (pintype "passive"))
      (node (ref "JP4") (pin "16") (pinfunction "16_16") (pintype "passive"))
    )
    (net (code "151") (name "Net-(CAM2-Pad4)") (class "Default")
      (node (ref "CAM2") (pin "4") (pinfunction "4_4") (pintype "passive"))
      (node (ref "JP3") (pin "2") (pinfunction "2_2") (pintype "passive"))
    )
    (net (code "152") (name "Net-(CAM2-Pad5)") (class "Default")
      (node (ref "CAM2") (pin "5") (pinfunction "5_5") (pintype "passive"))
      (node (ref "JP4") (pin "15") (pinfunction "15_15") (pintype "passive"))
    )
    (net (code "153") (name "Net-(CAM2-Pad6)") (class "Default")
      (node (ref "CAM2") (pin "6") (pinfunction "6_6") (pintype "passive"))
      (node (ref "JP3") (pin "3") (pinfunction "3_3") (pintype "passive"))
    )
    (net (code "154") (name "Net-(CAM2-Pad7)") (class "Default")
      (node (ref "CAM2") (pin "7") (pinfunction "7_7") (pintype "passive"))
      (node (ref "JP4") (pin "14") (pinfunction "14_14") (pintype "passive"))
    )
    (net (code "155") (name "Net-(CAM2-Pad8)") (class "Default")
      (node (ref "CAM2") (pin "8") (pinfunction "8_8") (pintype "passive"))
      (node (ref "JP3") (pin "4") (pinfunction "4_4") (pintype "passive"))
    )
    (net (code "156") (name "Net-(CAM2-Pad9)") (class "Default")
      (node (ref "CAM2") (pin "9") (pinfunction "9_9") (pintype "passive"))
      (node (ref "JP4") (pin "13") (pinfunction "13_13") (pintype "passive"))
    )
    (net (code "157") (name "Net-(CAM2-Pad10)") (class "Default")
      (node (ref "CAM2") (pin "10") (pinfunction "10_10") (pintype "passive"))
      (node (ref "JP3") (pin "5") (pinfunction "5_5") (pintype "passive"))
    )
    (net (code "158") (name "Net-(CAM2-Pad11)") (class "Default")
      (node (ref "CAM2") (pin "11") (pinfunction "11_11") (pintype "passive"))
      (node (ref "JP4") (pin "12") (pinfunction "12_12") (pintype "passive"))
    )
    (net (code "159") (name "Net-(CAM2-Pad12)") (class "Default")
      (node (ref "CAM2") (pin "12") (pinfunction "12_12") (pintype "passive"))
      (node (ref "JP3") (pin "6") (pinfunction "6_6") (pintype "passive"))
    )
    (net (code "160") (name "Net-(CAM2-Pad13)") (class "Default")
      (node (ref "CAM2") (pin "13") (pinfunction "13_13") (pintype "passive"))
      (node (ref "JP4") (pin "11") (pinfunction "11_11") (pintype "passive"))
    )
    (net (code "161") (name "Net-(CAM2-Pad14)") (class "Default")
      (node (ref "CAM2") (pin "14") (pinfunction "14_14") (pintype "passive"))
      (node (ref "JP3") (pin "7") (pinfunction "7_7") (pintype "passive"))
    )
    (net (code "162") (name "Net-(CAM2-Pad15)") (class "Default")
      (node (ref "CAM2") (pin "15") (pinfunction "15_15") (pintype "passive"))
      (node (ref "JP4") (pin "10") (pinfunction "10_10") (pintype "passive"))
    )
    (net (code "163") (name "Net-(CAM2-Pad16)") (class "Default")
      (node (ref "CAM2") (pin "16") (pinfunction "16_16") (pintype "passive"))
      (node (ref "JP3") (pin "8") (pinfunction "8_8") (pintype "passive"))
    )
    (net (code "164") (name "Net-(CAM2-Pad17)") (class "Default")
      (node (ref "CAM2") (pin "17") (pinfunction "17_17") (pintype "passive"))
      (node (ref "JP4") (pin "9") (pinfunction "9_9") (pintype "passive"))
    )
    (net (code "165") (name "Net-(CAM2-Pad18)") (class "Default")
      (node (ref "CAM2") (pin "18") (pinfunction "18_18") (pintype "passive"))
      (node (ref "JP3") (pin "9") (pinfunction "9_9") (pintype "passive"))
    )
    (net (code "166") (name "Net-(CAM2-Pad19)") (class "Default")
      (node (ref "CAM2") (pin "19") (pinfunction "19_19") (pintype "passive"))
      (node (ref "JP4") (pin "8") (pinfunction "8_8") (pintype "passive"))
    )
    (net (code "167") (name "Net-(CAM2-Pad20)") (class "Default")
      (node (ref "CAM2") (pin "20") (pinfunction "20_20") (pintype "passive"))
      (node (ref "JP3") (pin "10") (pinfunction "10_10") (pintype "passive"))
    )
    (net (code "168") (name "Net-(CAM2-Pad21)") (class "Default")
      (node (ref "CAM2") (pin "21") (pinfunction "21_21") (pintype "passive"))
      (node (ref "JP4") (pin "7") (pinfunction "7_7") (pintype "passive"))
    )
    (net (code "169") (name "Net-(CAM2-Pad22)") (class "Default")
      (node (ref "CAM2") (pin "22") (pinfunction "22_22") (pintype "passive"))
      (node (ref "JP3") (pin "11") (pinfunction "11_11") (pintype "passive"))
    )
    (net (code "170") (name "Net-(CAM2-Pad23)") (class "Default")
      (node (ref "CAM2") (pin "23") (pinfunction "23_23") (pintype "passive"))
      (node (ref "JP4") (pin "6") (pinfunction "6_6") (pintype "passive"))
    )
    (net (code "171") (name "Net-(CAM2-Pad24)") (class "Default")
      (node (ref "CAM2") (pin "24") (pinfunction "24_24") (pintype "passive"))
      (node (ref "JP3") (pin "12") (pinfunction "12_12") (pintype "passive"))
    )
    (net (code "172") (name "Net-(CAM2-Pad25)") (class "Default")
      (node (ref "CAM2") (pin "25") (pinfunction "25_25") (pintype "passive"))
      (node (ref "JP4") (pin "5") (pinfunction "5_5") (pintype "passive"))
    )
    (net (code "173") (name "Net-(CAM2-Pad26)") (class "Default")
      (node (ref "CAM2") (pin "26") (pinfunction "26_26") (pintype "passive"))
      (node (ref "JP3") (pin "13") (pinfunction "13_13") (pintype "passive"))
    )
    (net (code "174") (name "Net-(CAM2-Pad27)") (class "Default")
      (node (ref "CAM2") (pin "27") (pinfunction "27_27") (pintype "passive"))
      (node (ref "JP4") (pin "4") (pinfunction "4_4") (pintype "passive"))
    )
    (net (code "175") (name "Net-(CAM2-Pad28)") (class "Default")
      (node (ref "CAM2") (pin "28") (pinfunction "28_28") (pintype "passive"))
      (node (ref "JP3") (pin "14") (pinfunction "14_14") (pintype "passive"))
    )
    (net (code "176") (name "Net-(CAM2-Pad29)") (class "Default")
      (node (ref "CAM2") (pin "29") (pinfunction "29_29") (pintype "passive"))
      (node (ref "JP4") (pin "3") (pinfunction "3_3") (pintype "passive"))
    )
    (net (code "177") (name "Net-(CAM2-Pad30)") (class "Default")
      (node (ref "CAM2") (pin "30") (pinfunction "30_30") (pintype "passive"))
      (node (ref "JP3") (pin "15") (pinfunction "15_15") (pintype "passive"))
    )
    (net (code "178") (name "Net-(CAM2-Pad31)") (class "Default")
      (node (ref "CAM2") (pin "31") (pinfunction "31_31") (pintype "passive"))
      (node (ref "JP4") (pin "2") (pinfunction "2_2") (pintype "passive"))
    )
    (net (code "179") (name "Net-(CAM2-Pad32)") (class "Default")
      (node (ref "CAM2") (pin "32") (pinfunction "32_32") (pintype "passive"))
      (node (ref "JP3") (pin "16") (pinfunction "16_16") (pintype "passive"))
    )
    (net (code "180") (name "Net-(CAM2-Pad33)") (class "Default")
      (node (ref "CAM2") (pin "33") (pinfunction "33_33") (pintype "passive"))
      (node (ref "JP4") (pin "1") (pinfunction "1_1") (pintype "passive"))
    )
    (net (code "181") (name "Net-(CAM2-Pad34)") (class "Default")
      (node (ref "CAM2") (pin "34") (pinfunction "34_34") (pintype "passive"))
      (node (ref "JP3") (pin "17") (pinfunction "17_17") (pintype "passive"))
    )
    (net (code "182") (name "unconnected-(CAM1_IN-Pad16)") (class "Default")
      (node (ref "CAM1_IN") (pin "16") (pinfunction "16_16") (pintype "passive"))
    )
    (net (code "183") (name "unconnected-(CAM1_IN-Pad17)") (class "Default")
      (node (ref "CAM1_IN") (pin "17") (pinfunction "17_17") (pintype "passive"))
    )
    (net (code "184") (name "unconnected-(CAM1_IN-Pad18)") (class "Default")
      (node (ref "CAM1_IN") (pin "18") (pinfunction "18_18") (pintype "passive"))
    )
    (net (code "185") (name "unconnected-(CAM1_IN-Pad19)") (class "Default")
      (node (ref "CAM1_IN") (pin "19") (pinfunction "19_19") (pintype "passive"))
    )
    (net (code "186") (name "unconnected-(CAM1_IN-Pad21)") (class "Default")
      (node (ref "CAM1_IN") (pin "21") (pinfunction "21_21") (pintype "passive"))
    )
    (net (code "187") (name "unconnected-(CAM1_IN-Pad23)") (class "Default")
      (node (ref "CAM1_IN") (pin "23") (pinfunction "23_23") (pintype "passive"))
    )
    (net (code "188") (name "unconnected-(CAM1_IN-Pad24)") (class "Default")
      (node (ref "CAM1_IN") (pin "24") (pinfunction "24_24") (pintype "passive"))
    )
    (net (code "189") (name "unconnected-(CAM1_IN-Pad30)") (class "Default")
      (node (ref "CAM1_IN") (pin "30") (pinfunction "30_30") (pintype "passive"))
    )
    (net (code "190") (name "unconnected-(CAM1_IN-Pad32)") (class "Default")
      (node (ref "CAM1_IN") (pin "32") (pinfunction "32_32") (pintype "passive"))
    )
    (net (code "191") (name "unconnected-(CAM1_IN-Pad33)") (class "Default")
      (node (ref "CAM1_IN") (pin "33") (pinfunction "33_33") (pintype "passive"))
    )
    (net (code "192") (name "unconnected-(CAM1_IN-Pad34)") (class "Default")
      (node (ref "CAM1_IN") (pin "34") (pinfunction "34_34") (pintype "passive"))
    )
    (net (code "193") (name "unconnected-(CAM2_IN-Pad16)") (class "Default")
      (node (ref "CAM2_IN") (pin "16") (pinfunction "16_16") (pintype "passive"))
    )
    (net (code "194") (name "unconnected-(CAM2_IN-Pad17)") (class "Default")
      (node (ref "CAM2_IN") (pin "17") (pinfunction "17_17") (pintype "passive"))
    )
    (net (code "195") (name "unconnected-(CAM2_IN-Pad18)") (class "Default")
      (node (ref "CAM2_IN") (pin "18") (pinfunction "18_18") (pintype "passive"))
    )
    (net (code "196") (name "unconnected-(CAM2_IN-Pad19)") (class "Default")
      (node (ref "CAM2_IN") (pin "19") (pinfunction "19_19") (pintype "passive"))
    )
    (net (code "197") (name "unconnected-(CAM2_IN-Pad21)") (class "Default")
      (node (ref "CAM2_IN") (pin "21") (pinfunction "21_21") (pintype "passive"))
    )
    (net (code "198") (name "unconnected-(CAM2_IN-Pad23)") (class "Default")
      (node (ref "CAM2_IN") (pin "23") (pinfunction "23_23") (pintype "passive"))
    )
    (net (code "199") (name "unconnected-(CAM2_IN-Pad24)") (class "Default")
      (node (ref "CAM2_IN") (pin "24") (pinfunction "24_24") (pintype "passive"))
    )
    (net (code "200") (name "unconnected-(CAM2_IN-Pad30)") (class "Default")
      (node (ref "CAM2_IN") (pin "30") (pinfunction "30_30") (pintype "passive"))
    )
    (net (code "201") (name "unconnected-(CAM2_IN-Pad32)") (class "Default")
      (node (ref "CAM2_IN") (pin "32") (pinfunction "32_32") (pintype "passive"))
    )
    (net (code "202") (name "unconnected-(CAM2_IN-Pad33)") (class "Default")
      (node (ref "CAM2_IN") (pin "33") (pinfunction "33_33") (pintype "passive"))
    )
    (net (code "203") (name "unconnected-(CAM2_IN-Pad34)") (class "Default")
      (node (ref "CAM2_IN") (pin "34") (pinfunction "34_34") (pintype "passive"))
    )
  )
)
